# VS1053-PCB.net
KiCad netlist of a schematic drawn in EAGLE
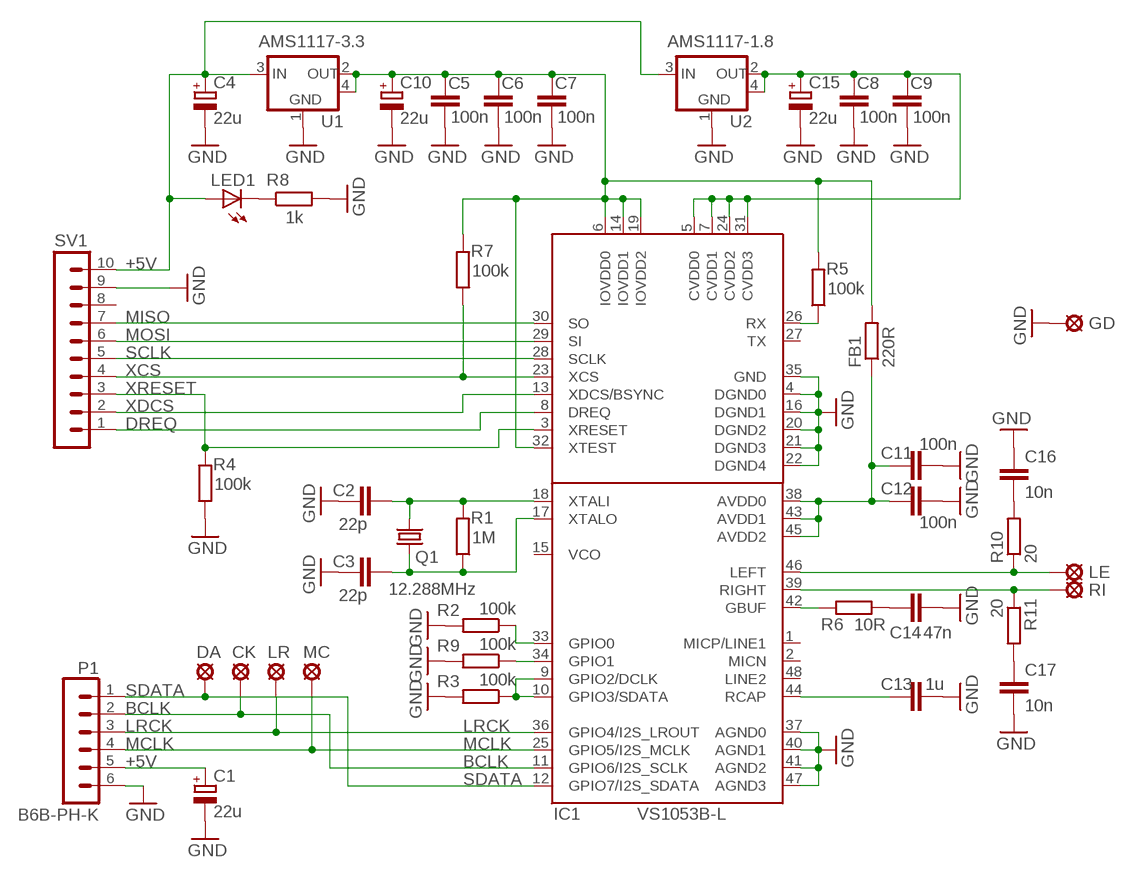
[diagram p0: schematic, sheet 1]

(export (version "E")
  (design (tool "Eeschema 10.0.6"))
  (components
    (comp (ref "C1")
      (value "22u")
      (footprint "eagle-import:CT3528")
      (libsource (lib "eagle-import") (part "CPOL-EUCT3528"))
    )
    (comp (ref "C2")
      (value "22p")
      (footprint "eagle-import:C0805")
      (libsource (lib "eagle-import") (part "C-EUC0805"))
    )
    (comp (ref "C3")
      (value "22p")
      (footprint "eagle-import:C0805")
      (libsource (lib "eagle-import") (part "C-EUC0805"))
    )
    (comp (ref "C4")
      (value "22u")
      (footprint "eagle-import:CT3528")
      (libsource (lib "eagle-import") (part "CPOL-EUCT3528"))
    )
    (comp (ref "C5")
      (value "100n")
      (footprint "eagle-import:C0805")
      (libsource (lib "eagle-import") (part "C-EUC0805"))
    )
    (comp (ref "C6")
      (value "100n")
      (footprint "eagle-import:C0805")
      (libsource (lib "eagle-import") (part "C-EUC0805"))
    )
    (comp (ref "C7")
      (value "100n")
      (footprint "eagle-import:C0805")
      (libsource (lib "eagle-import") (part "C-EUC0805"))
    )
    (comp (ref "C8")
      (value "100n")
      (footprint "eagle-import:C0805")
      (libsource (lib "eagle-import") (part "C-EUC0805"))
    )
    (comp (ref "C9")
      (value "100n")
      (footprint "eagle-import:C0805")
      (libsource (lib "eagle-import") (part "C-EUC0805"))
    )
    (comp (ref "C10")
      (value "22u")
      (footprint "eagle-import:CT3528")
      (libsource (lib "eagle-import") (part "CPOL-EUCT3528"))
    )
    (comp (ref "C11")
      (value "100n")
      (footprint "eagle-import:C0805")
      (libsource (lib "eagle-import") (part "C-EUC0805"))
    )
    (comp (ref "C12")
      (value "100n")
      (footprint "eagle-import:C0805")
      (libsource (lib "eagle-import") (part "C-EUC0805"))
    )
    (comp (ref "C13")
      (value "1u")
      (footprint "eagle-import:C0805")
      (libsource (lib "eagle-import") (part "C-EUC0805"))
    )
    (comp (ref "C14")
      (value "47n")
      (footprint "eagle-import:C0805")
      (libsource (lib "eagle-import") (part "C-EUC0805"))
    )
    (comp (ref "C15")
      (value "22u")
      (footprint "eagle-import:CT3528")
      (libsource (lib "eagle-import") (part "CPOL-EUCT3528"))
    )
    (comp (ref "C16")
      (value "10n")
      (footprint "eagle-import:C0603")
      (libsource (lib "eagle-import") (part "C-EUC0603"))
    )
    (comp (ref "C17")
      (value "10n")
      (footprint "eagle-import:C0603")
      (libsource (lib "eagle-import") (part "C-EUC0603"))
    )
    (comp (ref "CK")
      (value "SOLPAD-MINI")
      (footprint "eagle-import:SOLPAD-MINI")
      (libsource (lib "eagle-import") (part "SOLPAD-MINI"))
    )
    (comp (ref "DA")
      (value "SOLPAD-MINI")
      (footprint "eagle-import:SOLPAD-MINI")
      (libsource (lib "eagle-import") (part "SOLPAD-MINI"))
    )
    (comp (ref "FB1")
      (value "220R")
      (footprint "eagle-import:R0805")
      (libsource (lib "eagle-import") (part "R-EU_R0805"))
    )
    (comp (ref "GD")
      (value "LSP10-ROUND")
      (footprint "eagle-import:LSP10-ROUND")
      (libsource (lib "eagle-import") (part "LSP10-ROUND"))
    )
    (comp (ref "IC1")
      (value "VS1053B-L")
      (footprint "eagle-import:QFP50P900X900X160-48N")
      (libsource (lib "eagle-import") (part "VS1053B-L"))
    )
    (comp (ref "LE")
      (value "LSP10-ROUND")
      (footprint "eagle-import:LSP10-ROUND")
      (libsource (lib "eagle-import") (part "LSP10-ROUND"))
    )
    (comp (ref "LED1")
      (value "LEDCHIPLED_0805")
      (footprint "eagle-import:CHIPLED_0805")
      (libsource (lib "eagle-import") (part "LEDCHIPLED_0805"))
    )
    (comp (ref "LR")
      (value "SOLPAD-MINI")
      (footprint "eagle-import:SOLPAD-MINI")
      (libsource (lib "eagle-import") (part "SOLPAD-MINI"))
    )
    (comp (ref "MC")
      (value "SOLPAD-MINI")
      (footprint "eagle-import:SOLPAD-MINI")
      (libsource (lib "eagle-import") (part "SOLPAD-MINI"))
    )
    (comp (ref "P1")
      (value "B6B-PH-K")
      (footprint "eagle-import:B6B-PH-K")
      (libsource (lib "eagle-import") (part "B6B-PH-K"))
    )
    (comp (ref "Q1")
      (value "12.288MHz")
      (footprint "eagle-import:HC49_S")
      (libsource (lib "eagle-import") (part "CRYSTALHC49S"))
    )
    (comp (ref "R1")
      (value "1M")
      (footprint "eagle-import:R0805")
      (libsource (lib "eagle-import") (part "R-EU_R0805"))
    )
    (comp (ref "R2")
      (value "100k")
      (footprint "eagle-import:R0805")
      (libsource (lib "eagle-import") (part "R-EU_R0805"))
    )
    (comp (ref "R3")
      (value "100k")
      (footprint "eagle-import:R0805")
      (libsource (lib "eagle-import") (part "R-EU_R0805"))
    )
    (comp (ref "R4")
      (value "100k")
      (footprint "eagle-import:R0805")
      (libsource (lib "eagle-import") (part "R-EU_R0805"))
    )
    (comp (ref "R5")
      (value "100k")
      (footprint "eagle-import:R0805")
      (libsource (lib "eagle-import") (part "R-EU_R0805"))
    )
    (comp (ref "R6")
      (value "10R")
      (footprint "eagle-import:R0805")
      (libsource (lib "eagle-import") (part "R-EU_R0805"))
    )
    (comp (ref "R7")
      (value "100k")
      (footprint "eagle-import:R0805")
      (libsource (lib "eagle-import") (part "R-EU_R0805"))
    )
    (comp (ref "R8")
      (value "1k")
      (footprint "eagle-import:R0805")
      (libsource (lib "eagle-import") (part "R-EU_R0805"))
    )
    (comp (ref "R9")
      (value "100k")
      (footprint "eagle-import:R0805")
      (libsource (lib "eagle-import") (part "R-EU_R0805"))
    )
    (comp (ref "R10")
      (value "20")
      (footprint "eagle-import:R0603")
      (libsource (lib "eagle-import") (part "R-EU_R0603"))
    )
    (comp (ref "R11")
      (value "20")
      (footprint "eagle-import:R0603")
      (libsource (lib "eagle-import") (part "R-EU_R0603"))
    )
    (comp (ref "RI")
      (value "LSP10-ROUND")
      (footprint "eagle-import:LSP10-ROUND")
      (libsource (lib "eagle-import") (part "LSP10-ROUND"))
    )
    (comp (ref "SV1")
      (value "MA10-1-THIN")
      (footprint "eagle-import:MA10-1-THIN")
      (libsource (lib "eagle-import") (part "MA10-1-THIN"))
    )
    (comp (ref "U1")
      (value "AMS1117-3.3")
      (footprint "eagle-import:SOT223")
      (libsource (lib "eagle-import") (part "LT1117-S"))
    )
    (comp (ref "U2")
      (value "AMS1117-1.8")
      (footprint "eagle-import:SOT223")
      (libsource (lib "eagle-import") (part "LT1117-S"))
    )
  )
  (nets
    (net (code "1") (name "/+5V") (class "Default")
      (node (ref "C1") (pin "+") (pinfunction "+_+") (pintype "passive"))
      (node (ref "C4") (pin "+") (pinfunction "+_+") (pintype "passive"))
      (node (ref "LED1") (pin "A") (pinfunction "A_A") (pintype "passive"))
      (node (ref "P1") (pin "5") (pinfunction "5_5") (pintype "passive"))
      (node (ref "SV1") (pin "10") (pinfunction "10_10") (pintype "passive"))
      (node (ref "U1") (pin "3") (pinfunction "IN_3") (pintype "input"))
      (node (ref "U2") (pin "3") (pinfunction "IN_3") (pintype "input"))
    )
    (net (code "2") (name "/BCLK") (class "Default")
      (node (ref "CK") (pin "1") (pinfunction "SOLPAD_1") (pintype "passive"))
      (node (ref "IC1") (pin "11") (pinfunction "GPIO6/I2S_SCLK_11") (pintype "bidirectional"))
      (node (ref "P1") (pin "2") (pinfunction "2_2") (pintype "passive"))
    )
    (net (code "3") (name "/DREQ") (class "Default")
      (node (ref "IC1") (pin "8") (pinfunction "DREQ_8") (pintype "bidirectional"))
      (node (ref "SV1") (pin "1") (pinfunction "1_1") (pintype "passive"))
    )
    (net (code "4") (name "/LRCK") (class "Default")
      (node (ref "IC1") (pin "36") (pinfunction "GPIO4/I2S_LROUT_36") (pintype "bidirectional"))
      (node (ref "LR") (pin "1") (pinfunction "SOLPAD_1") (pintype "passive"))
      (node (ref "P1") (pin "3") (pinfunction "3_3") (pintype "passive"))
    )
    (net (code "5") (name "/MCLK") (class "Default")
      (node (ref "IC1") (pin "25") (pinfunction "GPIO5/I2S_MCLK_25") (pintype "bidirectional"))
      (node (ref "MC") (pin "1") (pinfunction "SOLPAD_1") (pintype "passive"))
      (node (ref "P1") (pin "4") (pinfunction "4_4") (pintype "passive"))
    )
    (net (code "6") (name "/MISO") (class "Default")
      (node (ref "IC1") (pin "30") (pinfunction "SO_30") (pintype "bidirectional"))
      (node (ref "SV1") (pin "7") (pinfunction "7_7") (pintype "passive"))
    )
    (net (code "7") (name "/MOSI") (class "Default")
      (node (ref "IC1") (pin "29") (pinfunction "SI_29") (pintype "bidirectional"))
      (node (ref "SV1") (pin "6") (pinfunction "6_6") (pintype "passive"))
    )
    (net (code "8") (name "/SCLK") (class "Default")
      (node (ref "IC1") (pin "28") (pinfunction "SCLK_28") (pintype "bidirectional"))
      (node (ref "SV1") (pin "5") (pinfunction "5_5") (pintype "passive"))
    )
    (net (code "9") (name "/SDATA") (class "Default")
      (node (ref "DA") (pin "1") (pinfunction "SOLPAD_1") (pintype "passive"))
      (node (ref "IC1") (pin "12") (pinfunction "GPIO7/I2S_SDATA_12") (pintype "bidirectional"))
      (node (ref "P1") (pin "1") (pinfunction "1_1") (pintype "passive"))
    )
    (net (code "10") (name "/XCS") (class "Default")
      (node (ref "IC1") (pin "23") (pinfunction "XCS_23") (pintype "bidirectional"))
      (node (ref "R7") (pin "1") (pinfunction "1_1") (pintype "passive"))
      (node (ref "SV1") (pin "4") (pinfunction "4_4") (pintype "passive"))
    )
    (net (code "11") (name "/XDCS") (class "Default")
      (node (ref "IC1") (pin "13") (pinfunction "XDCS/BSYNC_13") (pintype "bidirectional"))
      (node (ref "SV1") (pin "2") (pinfunction "2_2") (pintype "passive"))
    )
    (net (code "12") (name "/XRESET") (class "Default")
      (node (ref "IC1") (pin "3") (pinfunction "XRESET_3") (pintype "bidirectional"))
      (node (ref "R4") (pin "2") (pinfunction "2_2") (pintype "passive"))
      (node (ref "SV1") (pin "3") (pinfunction "3_3") (pintype "passive"))
    )
    (net (code "13") (name "GND") (class "Default")
      (node (ref "C1") (pin "-") (pinfunction "-_-") (pintype "passive"))
      (node (ref "C10") (pin "-") (pinfunction "-_-") (pintype "passive"))
      (node (ref "C11") (pin "2") (pinfunction "2_2") (pintype "passive"))
      (node (ref "C12") (pin "2") (pinfunction "2_2") (pintype "passive"))
      (node (ref "C13") (pin "2") (pinfunction "2_2") (pintype "passive"))
      (node (ref "C14") (pin "2") (pinfunction "2_2") (pintype "passive"))
      (node (ref "C15") (pin "-") (pinfunction "-_-") (pintype "passive"))
      (node (ref "C16") (pin "1") (pinfunction "1_1") (pintype "passive"))
      (node (ref "C17") (pin "2") (pinfunction "2_2") (pintype "passive"))
      (node (ref "C2") (pin "1") (pinfunction "1_1") (pintype "passive"))
      (node (ref "C3") (pin "1") (pinfunction "1_1") (pintype "passive"))
      (node (ref "C4") (pin "-") (pinfunction "-_-") (pintype "passive"))
      (node (ref "C5") (pin "2") (pinfunction "2_2") (pintype "passive"))
      (node (ref "C6") (pin "2") (pinfunction "2_2") (pintype "passive"))
      (node (ref "C7") (pin "2") (pinfunction "2_2") (pintype "passive"))
      (node (ref "C8") (pin "2") (pinfunction "2_2") (pintype "passive"))
      (node (ref "C9") (pin "2") (pinfunction "2_2") (pintype "passive"))
      (node (ref "GD") (pin "MP") (pinfunction "SOLPAD_MP") (pintype "passive"))
      (node (ref "IC1") (pin "16") (pinfunction "DGND1_16") (pintype "bidirectional"))
      (node (ref "IC1") (pin "20") (pinfunction "DGND2_20") (pintype "bidirectional"))
      (node (ref "IC1") (pin "21") (pinfunction "DGND3_21") (pintype "bidirectional"))
      (node (ref "IC1") (pin "22") (pinfunction "DGND4_22") (pintype "bidirectional"))
      (node (ref "IC1") (pin "35") (pinfunction "GND_35") (pintype "bidirectional"))
      (node (ref "IC1") (pin "37") (pinfunction "AGND0_37") (pintype "bidirectional"))
      (node (ref "IC1") (pin "4") (pinfunction "DGND0_4") (pintype "bidirectional"))
      (node (ref "IC1") (pin "40") (pinfunction "AGND1_40") (pintype "bidirectional"))
      (node (ref "IC1") (pin "41") (pinfunction "AGND2_41") (pintype "bidirectional"))
      (node (ref "IC1") (pin "47") (pinfunction "AGND3_47") (pintype "bidirectional"))
      (node (ref "P1") (pin "6") (pinfunction "6_6") (pintype "passive"))
      (node (ref "R2") (pin "2") (pinfunction "2_2") (pintype "passive"))
      (node (ref "R3") (pin "2") (pinfunction "2_2") (pintype "passive"))
      (node (ref "R4") (pin "1") (pinfunction "1_1") (pintype "passive"))
      (node (ref "R8") (pin "2") (pinfunction "2_2") (pintype "passive"))
      (node (ref "R9") (pin "2") (pinfunction "2_2") (pintype "passive"))
      (node (ref "SV1") (pin "9") (pinfunction "9_9") (pintype "passive"))
      (node (ref "U1") (pin "1") (pinfunction "GND_1") (pintype "input"))
      (node (ref "U2") (pin "1") (pinfunction "GND_1") (pintype "input"))
    )
    (net (code "14") (name "Net-(C14-Pad1)") (class "Default")
      (node (ref "C14") (pin "1") (pinfunction "1_1") (pintype "passive"))
      (node (ref "R6") (pin "2") (pinfunction "2_2") (pintype "passive"))
    )
    (net (code "15") (name "Net-(C16-Pad2)") (class "Default")
      (node (ref "C16") (pin "2") (pinfunction "2_2") (pintype "passive"))
      (node (ref "R10") (pin "2") (pinfunction "2_2") (pintype "passive"))
    )
    (net (code "16") (name "Net-(C17-Pad1)") (class "Default")
      (node (ref "C17") (pin "1") (pinfunction "1_1") (pintype "passive"))
      (node (ref "R11") (pin "2") (pinfunction "2_2") (pintype "passive"))
    )
    (net (code "17") (name "Net-(IC1-AVDD0)") (class "Default")
      (node (ref "C11") (pin "1") (pinfunction "1_1") (pintype "passive"))
      (node (ref "C12") (pin "1") (pinfunction "1_1") (pintype "passive"))
      (node (ref "FB1") (pin "1") (pinfunction "1_1") (pintype "passive"))
      (node (ref "IC1") (pin "38") (pinfunction "AVDD0_38") (pintype "bidirectional"))
      (node (ref "IC1") (pin "43") (pinfunction "AVDD1_43") (pintype "bidirectional"))
      (node (ref "IC1") (pin "45") (pinfunction "AVDD2_45") (pintype "bidirectional"))
    )
    (net (code "18") (name "Net-(IC1-CVDD0)") (class "Default")
      (node (ref "C15") (pin "+") (pinfunction "+_+") (pintype "passive"))
      (node (ref "C8") (pin "1") (pinfunction "1_1") (pintype "passive"))
      (node (ref "C9") (pin "1") (pinfunction "1_1") (pintype "passive"))
      (node (ref "IC1") (pin "24") (pinfunction "CVDD2_24") (pintype "bidirectional"))
      (node (ref "IC1") (pin "31") (pinfunction "CVDD3_31") (pintype "bidirectional"))
      (node (ref "IC1") (pin "5") (pinfunction "CVDD0_5") (pintype "bidirectional"))
      (node (ref "IC1") (pin "7") (pinfunction "CVDD1_7") (pintype "bidirectional"))
      (node (ref "U2") (pin "2") (pinfunction "OUT_2") (pintype "passive"))
      (node (ref "U2") (pin "4") (pinfunction "TAB_4") (pintype "passive"))
    )
    (net (code "19") (name "Net-(IC1-GBUF)") (class "Default")
      (node (ref "IC1") (pin "42") (pinfunction "GBUF_42") (pintype "bidirectional"))
      (node (ref "R6") (pin "1") (pinfunction "1_1") (pintype "passive"))
    )
    (net (code "20") (name "Net-(IC1-GPIO0)") (class "Default")
      (node (ref "IC1") (pin "33") (pinfunction "GPIO0_33") (pintype "bidirectional"))
      (node (ref "R2") (pin "1") (pinfunction "1_1") (pintype "passive"))
    )
    (net (code "21") (name "Net-(IC1-GPIO1)") (class "Default")
      (node (ref "IC1") (pin "34") (pinfunction "GPIO1_34") (pintype "bidirectional"))
      (node (ref "R9") (pin "1") (pinfunction "1_1") (pintype "passive"))
    )
    (net (code "22") (name "Net-(IC1-GPIO2{slash}DCLK)") (class "Default")
      (node (ref "IC1") (pin "10") (pinfunction "GPIO3/SDATA_10") (pintype "bidirectional"))
      (node (ref "IC1") (pin "9") (pinfunction "GPIO2/DCLK_9") (pintype "bidirectional"))
      (node (ref "R3") (pin "1") (pinfunction "1_1") (pintype "passive"))
    )
    (net (code "23") (name "Net-(IC1-IOVDD0)") (class "Default")
      (node (ref "C10") (pin "+") (pinfunction "+_+") (pintype "passive"))
      (node (ref "C5") (pin "1") (pinfunction "1_1") (pintype "passive"))
      (node (ref "C6") (pin "1") (pinfunction "1_1") (pintype "passive"))
      (node (ref "C7") (pin "1") (pinfunction "1_1") (pintype "passive"))
      (node (ref "FB1") (pin "2") (pinfunction "2_2") (pintype "passive"))
      (node (ref "IC1") (pin "14") (pinfunction "IOVDD1_14") (pintype "bidirectional"))
      (node (ref "IC1") (pin "19") (pinfunction "IOVDD2_19") (pintype "bidirectional"))
      (node (ref "IC1") (pin "32") (pinfunction "XTEST_32") (pintype "bidirectional"))
      (node (ref "IC1") (pin "6") (pinfunction "IOVDD0_6") (pintype "bidirectional"))
      (node (ref "R5") (pin "2") (pinfunction "2_2") (pintype "passive"))
      (node (ref "R7") (pin "2") (pinfunction "2_2") (pintype "passive"))
      (node (ref "U1") (pin "2") (pinfunction "OUT_2") (pintype "passive"))
      (node (ref "U1") (pin "4") (pinfunction "TAB_4") (pintype "passive"))
    )
    (net (code "24") (name "Net-(IC1-LEFT)") (class "Default")
      (node (ref "IC1") (pin "46") (pinfunction "LEFT_46") (pintype "bidirectional"))
      (node (ref "LE") (pin "MP") (pinfunction "SOLPAD_MP") (pintype "passive"))
      (node (ref "R10") (pin "1") (pinfunction "1_1") (pintype "passive"))
    )
    (net (code "25") (name "Net-(IC1-RCAP)") (class "Default")
      (node (ref "C13") (pin "1") (pinfunction "1_1") (pintype "passive"))
      (node (ref "IC1") (pin "44") (pinfunction "RCAP_44") (pintype "bidirectional"))
    )
    (net (code "26") (name "Net-(IC1-RIGHT)") (class "Default")
      (node (ref "IC1") (pin "39") (pinfunction "RIGHT_39") (pintype "bidirectional"))
      (node (ref "R11") (pin "1") (pinfunction "1_1") (pintype "passive"))
      (node (ref "RI") (pin "MP") (pinfunction "SOLPAD_MP") (pintype "passive"))
    )
    (net (code "27") (name "Net-(IC1-RX)") (class "Default")
      (node (ref "IC1") (pin "26") (pinfunction "RX_26") (pintype "bidirectional"))
      (node (ref "R5") (pin "1") (pinfunction "1_1") (pintype "passive"))
    )
    (net (code "28") (name "Net-(IC1-XTALI)") (class "Default")
      (node (ref "C2") (pin "2") (pinfunction "2_2") (pintype "passive"))
      (node (ref "IC1") (pin "18") (pinfunction "XTALI_18") (pintype "bidirectional"))
      (node (ref "Q1") (pin "2") (pinfunction "2_2") (pintype "passive"))
      (node (ref "R1") (pin "2") (pinfunction "2_2") (pintype "passive"))
    )
    (net (code "29") (name "Net-(IC1-XTALO)") (class "Default")
      (node (ref "C3") (pin "2") (pinfunction "2_2") (pintype "passive"))
      (node (ref "IC1") (pin "17") (pinfunction "XTALO_17") (pintype "bidirectional"))
      (node (ref "Q1") (pin "1") (pinfunction "1_1") (pintype "passive"))
      (node (ref "R1") (pin "1") (pinfunction "1_1") (pintype "passive"))
    )
    (net (code "30") (name "Net-(LED1-PadC)") (class "Default")
      (node (ref "LED1") (pin "C") (pinfunction "C_C") (pintype "passive"))
      (node (ref "R8") (pin "1") (pinfunction "1_1") (pintype "passive"))
    )
    (net (code "31") (name "unconnected-(IC1-LINE2-Pad48)") (class "Default")
      (node (ref "IC1") (pin "48") (pinfunction "LINE2_48") (pintype "bidirectional"))
    )
    (net (code "32") (name "unconnected-(IC1-MICN-Pad2)") (class "Default")
      (node (ref "IC1") (pin "2") (pinfunction "MICN_2") (pintype "bidirectional"))
    )
    (net (code "33") (name "unconnected-(IC1-MICP{slash}LINE1-Pad1)") (class "Default")
      (node (ref "IC1") (pin "1") (pinfunction "MICP/LINE1_1") (pintype "bidirectional"))
    )
    (net (code "34") (name "unconnected-(IC1-TX-Pad27)") (class "Default")
      (node (ref "IC1") (pin "27") (pinfunction "TX_27") (pintype "bidirectional"))
    )
    (net (code "35") (name "unconnected-(IC1-VCO-Pad15)") (class "Default")
      (node (ref "IC1") (pin "15") (pinfunction "VCO_15") (pintype "bidirectional"))
    )
    (net (code "36") (name "unconnected-(SV1-Pad8)") (class "Default")
      (node (ref "SV1") (pin "8") (pinfunction "8_8") (pintype "passive"))
    )
  )
)
